# PoE.net
KiCad netlist of a schematic drawn in Altium Designer
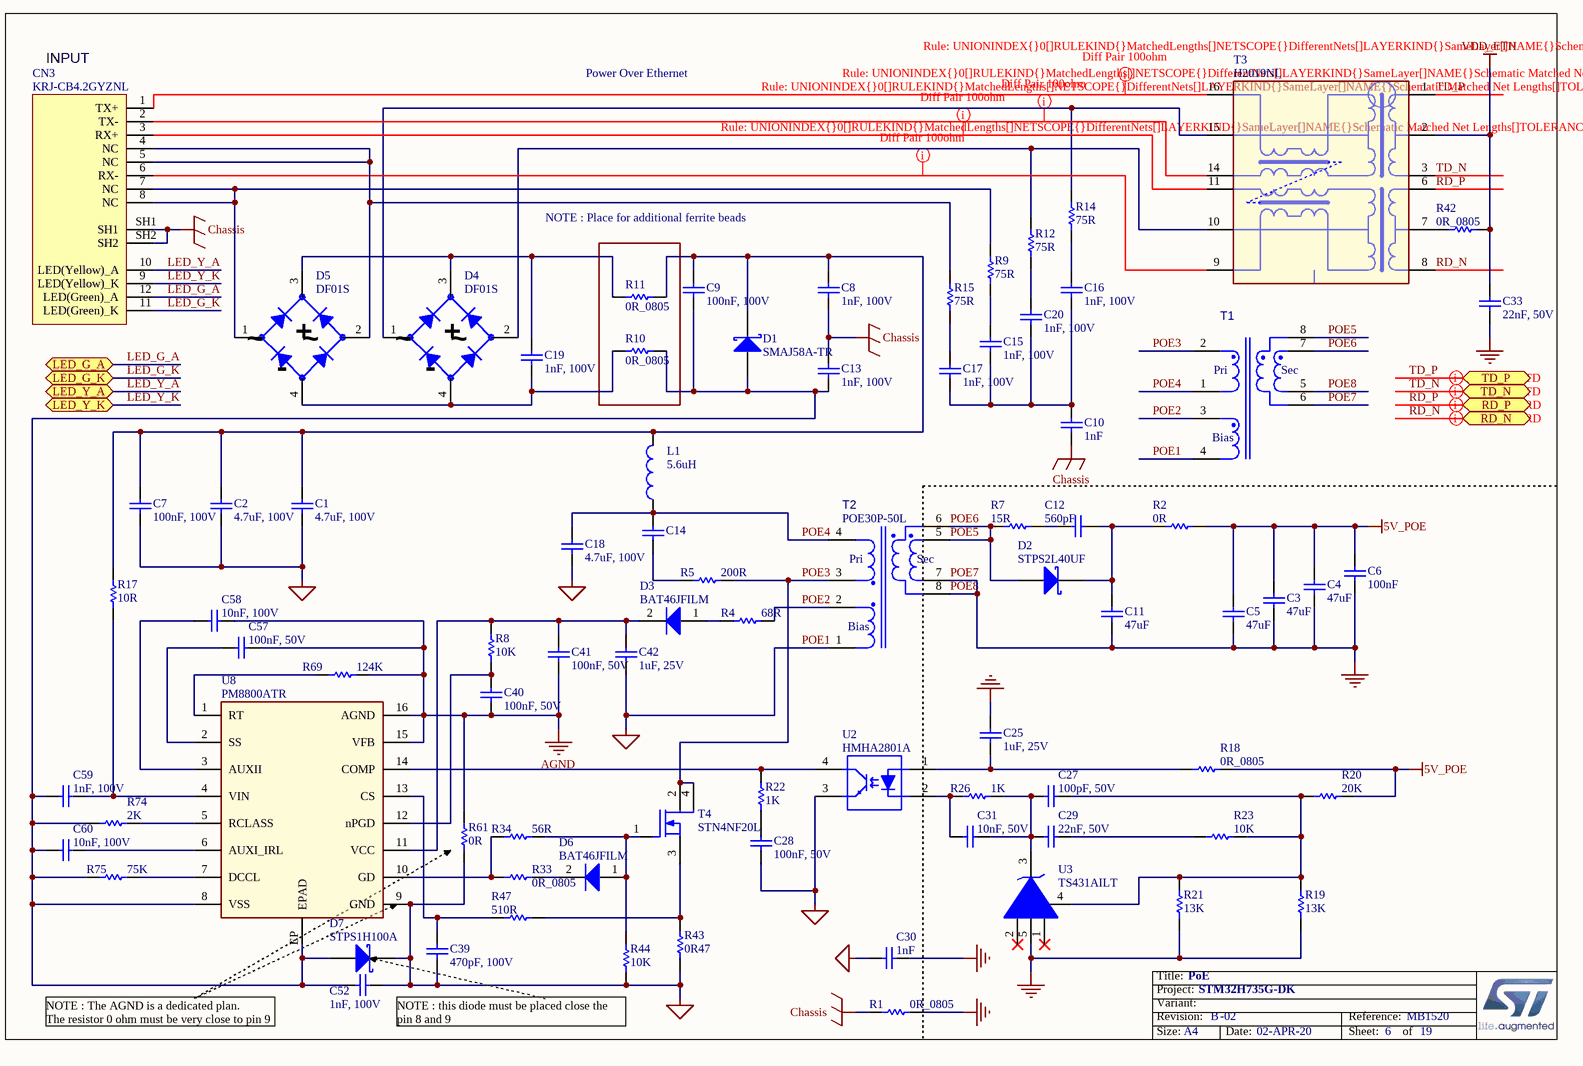
[diagram p0: PoE.SchDoc]

(export (version "E")
  (design (tool "Eeschema 10.0.6"))
  (components
    (comp (ref "C1")
      (value "4.7uF, 100V")
      (footprint "C1210")
      (description "Capacitor,4.7uF,100V, X7S,20%,1210")
      (fields
        (field (name "INTERNAL_PART_NUMBER") "MCD-01172")
        (field (name "MANUFACTURER_PART_NUMBER") "12101Z475MAT2A")
        (field (name "PROVIDED_BY") "SUBCO")
      )
      (libsource (lib "MCD_PARTS_database") (part "Capacitor"))
    )
    (comp (ref "C2")
      (value "4.7uF, 100V")
      (footprint "C1210")
      (description "Capacitor,4.7uF,100V, X7S,20%,1210")
      (fields
        (field (name "INTERNAL_PART_NUMBER") "MCD-01172")
        (field (name "MANUFACTURER_PART_NUMBER") "12101Z475MAT2A")
        (field (name "PROVIDED_BY") "SUBCO")
      )
      (libsource (lib "MCD_PARTS_database") (part "Capacitor"))
    )
    (comp (ref "C3")
      (value "47uF")
      (footprint "C0805")
      (description "Capacitor, MLCC, 47uF, 10V, X5R, 20%, 0805, T=1,25mm")
      (fields
        (field (name "INTERNAL_PART_NUMBER") "MCD-00204")
        (field (name "MANUFACTURER_PART_NUMBER") "GRM21BR61A476ME15K")
        (field (name "PROVIDED_BY") "SUBCO")
      )
      (libsource (lib "MCD_PARTS_database") (part "Capacitor"))
    )
    (comp (ref "C4")
      (value "47uF")
      (footprint "C0805")
      (description "Capacitor, MLCC, 47uF, 10V, X5R, 20%, 0805, T=1,25mm")
      (fields
        (field (name "INTERNAL_PART_NUMBER") "MCD-00204")
        (field (name "MANUFACTURER_PART_NUMBER") "GRM21BR61A476ME15K")
        (field (name "PROVIDED_BY") "SUBCO")
      )
      (libsource (lib "MCD_PARTS_database") (part "Capacitor"))
    )
    (comp (ref "C5")
      (value "47uF")
      (footprint "C0805")
      (description "Capacitor, MLCC, 47uF, 10V, X5R, 20%, 0805, T=1,25mm")
      (fields
        (field (name "INTERNAL_PART_NUMBER") "MCD-00204")
        (field (name "MANUFACTURER_PART_NUMBER") "GRM21BR61A476ME15K")
        (field (name "PROVIDED_BY") "SUBCO")
      )
      (libsource (lib "MCD_PARTS_database") (part "Capacitor"))
    )
    (comp (ref "C6")
      (value "100nF")
      (footprint "C0603")
      (description "Capacitor, MLCC, 100nF, 16V, X7R, 10%, 0603, T=0,8mm")
      (fields
        (field (name "INTERNAL_PART_NUMBER") "MCD-00211")
        (field (name "MANUFACTURER_PART_NUMBER") "CC0603KRX7R7BB104")
        (field (name "PROVIDED_BY") "SUBCO")
      )
      (libsource (lib "MCD_PARTS_database") (part "Capacitor"))
    )
    (comp (ref "C7")
      (value "100nF, 100V")
      (footprint "C0805")
      (description "Capacitor,100nF,100V,X7R,10%,0805")
      (fields
        (field (name "INTERNAL_PART_NUMBER") "MCD-01093")
        (field (name "MANUFACTURER_PART_NUMBER") "C2012X7R2A104K125AA")
        (field (name "PROVIDED_BY") "SUBCO")
      )
      (libsource (lib "MCD_PARTS_database") (part "Capacitor"))
    )
    (comp (ref "C8")
      (value "1nF, 100V")
      (footprint "C0603")
      (description "Capacitor,1nF,100V,X7R,10%,0603")
      (fields
        (field (name "INTERNAL_PART_NUMBER") "MCD-01091")
        (field (name "MANUFACTURER_PART_NUMBER") "CC0603KRX7R0BB102")
        (field (name "PROVIDED_BY") "SUBCO")
      )
      (libsource (lib "MCD_PARTS_database") (part "Capacitor"))
    )
    (comp (ref "C9")
      (value "100nF, 100V")
      (footprint "C0805")
      (description "Capacitor,100nF,100V,X7R,10%,0805")
      (fields
        (field (name "INTERNAL_PART_NUMBER") "MCD-01093")
        (field (name "MANUFACTURER_PART_NUMBER") "C2012X7R2A104K125AA")
        (field (name "PROVIDED_BY") "SUBCO")
      )
      (libsource (lib "MCD_PARTS_database") (part "Capacitor"))
    )
    (comp (ref "C10")
      (value "1nF")
      (footprint "C1206_H1P6")
      (description "Capacitor, MLCC, 1nF, 2KV, X7R, 10%, 1206, T=1,25mm")
      (fields
        (field (name "INTERNAL_PART_NUMBER") "MCD-00722")
        (field (name "MANUFACTURER_PART_NUMBER") "CC1206KKX7RDBB102")
        (field (name "PROVIDED_BY") "SUBCO")
      )
      (libsource (lib "MCD_PARTS_database") (part "Capacitor"))
    )
    (comp (ref "C11")
      (value "47uF")
      (footprint "C0805")
      (description "Capacitor, MLCC, 47uF, 10V, X5R, 20%, 0805, T=1,25mm")
      (fields
        (field (name "INTERNAL_PART_NUMBER") "MCD-00204")
        (field (name "MANUFACTURER_PART_NUMBER") "GRM21BR61A476ME15K")
        (field (name "PROVIDED_BY") "SUBCO")
      )
      (libsource (lib "MCD_PARTS_database") (part "Capacitor"))
    )
    (comp (ref "C12")
      (value "560pF")
      (footprint "C0603")
      (description "Capacitor,560pF,16V,X7R,10%,0603")
      (fields
        (field (name "INTERNAL_PART_NUMBER") "MCD-01095")
        (field (name "MANUFACTURER_PART_NUMBER") "0603YC561KAT2A")
        (field (name "PROVIDED_BY") "SUBCO")
      )
      (libsource (lib "MCD_PARTS_database") (part "Capacitor"))
    )
    (comp (ref "C13")
      (value "1nF, 100V")
      (footprint "C0603")
      (description "Capacitor,1nF,100V,X7R,10%,0603")
      (fields
        (field (name "INTERNAL_PART_NUMBER") "MCD-01091")
        (field (name "MANUFACTURER_PART_NUMBER") "CC0603KRX7R0BB102")
        (field (name "PROVIDED_BY") "SUBCO")
      )
      (libsource (lib "MCD_PARTS_database") (part "Capacitor"))
    )
    (comp (ref "C14")
      (value "Capacitor")
      (footprint "C0603")
      (description "Capacitor,27pF,100V,NPO,5%,0603")
      (fields
        (field (name "INTERNAL_PART_NUMBER") "MCD-01096")
        (field (name "MANUFACTURER_PART_NUMBER") "CC0603JRNPO0BN270")
        (field (name "PROVIDED_BY") "SUBCO")
      )
      (libsource (lib "MCD_PARTS_database") (part "Capacitor"))
    )
    (comp (ref "C15")
      (value "1nF, 100V")
      (footprint "C0603")
      (description "Capacitor,1nF,100V,X7R,10%,0603")
      (fields
        (field (name "INTERNAL_PART_NUMBER") "MCD-01091")
        (field (name "MANUFACTURER_PART_NUMBER") "CC0603KRX7R0BB102")
        (field (name "PROVIDED_BY") "SUBCO")
      )
      (libsource (lib "MCD_PARTS_database") (part "Capacitor"))
    )
    (comp (ref "C16")
      (value "1nF, 100V")
      (footprint "C0603")
      (description "Capacitor,1nF,100V,X7R,10%,0603")
      (fields
        (field (name "INTERNAL_PART_NUMBER") "MCD-01091")
        (field (name "MANUFACTURER_PART_NUMBER") "CC0603KRX7R0BB102")
        (field (name "PROVIDED_BY") "SUBCO")
      )
      (libsource (lib "MCD_PARTS_database") (part "Capacitor"))
    )
    (comp (ref "C17")
      (value "1nF, 100V")
      (footprint "C0603")
      (description "Capacitor,1nF,100V,X7R,10%,0603")
      (fields
        (field (name "INTERNAL_PART_NUMBER") "MCD-01091")
        (field (name "MANUFACTURER_PART_NUMBER") "CC0603KRX7R0BB102")
        (field (name "PROVIDED_BY") "SUBCO")
      )
      (libsource (lib "MCD_PARTS_database") (part "Capacitor"))
    )
    (comp (ref "C18")
      (value "4.7uF, 100V")
      (footprint "C1210")
      (description "Capacitor,4.7uF,100V, X7S,20%,1210")
      (fields
        (field (name "INTERNAL_PART_NUMBER") "MCD-01172")
        (field (name "MANUFACTURER_PART_NUMBER") "12101Z475MAT2A")
        (field (name "PROVIDED_BY") "SUBCO")
      )
      (libsource (lib "MCD_PARTS_database") (part "Capacitor"))
    )
    (comp (ref "C19")
      (value "1nF, 100V")
      (footprint "C0603")
      (description "Capacitor,1nF,100V,X7R,10%,0603")
      (fields
        (field (name "INTERNAL_PART_NUMBER") "MCD-01091")
        (field (name "MANUFACTURER_PART_NUMBER") "CC0603KRX7R0BB102")
        (field (name "PROVIDED_BY") "SUBCO")
      )
      (libsource (lib "MCD_PARTS_database") (part "Capacitor"))
    )
    (comp (ref "C20")
      (value "1nF, 100V")
      (footprint "C0603")
      (description "Capacitor,1nF,100V,X7R,10%,0603")
      (fields
        (field (name "INTERNAL_PART_NUMBER") "MCD-01091")
        (field (name "MANUFACTURER_PART_NUMBER") "CC0603KRX7R0BB102")
        (field (name "PROVIDED_BY") "SUBCO")
      )
      (libsource (lib "MCD_PARTS_database") (part "Capacitor"))
    )
    (comp (ref "C25")
      (value "1uF, 25V")
      (footprint "C0603")
      (description "Capacitor,1uF,25V,X5R,10%,0603")
      (fields
        (field (name "INTERNAL_PART_NUMBER") "MCD-01100")
        (field (name "MANUFACTURER_PART_NUMBER") "CC0603KRX5R8BB105")
        (field (name "PROVIDED_BY") "SUBCO")
      )
      (libsource (lib "MCD_PARTS_database") (part "Capacitor"))
    )
    (comp (ref "C27")
      (value "100pF, 50V")
      (footprint "C0603")
      (description "Capacitor,100pF,50V,X7R,10%,0603")
      (fields
        (field (name "INTERNAL_PART_NUMBER") "MCD-01101")
        (field (name "MANUFACTURER_PART_NUMBER") "06035C101JAT4A")
        (field (name "PROVIDED_BY") "SUBCO")
      )
      (libsource (lib "MCD_PARTS_database") (part "Capacitor"))
    )
    (comp (ref "C28")
      (value "100nF, 50V")
      (footprint "C0603")
      (description "Capacitor,100nF,50V,X7R,10%,0603")
      (fields
        (field (name "INTERNAL_PART_NUMBER") "MCD-01099")
        (field (name "MANUFACTURER_PART_NUMBER") "CC0603KRX7R9BB104")
        (field (name "PROVIDED_BY") "SUBCO")
      )
      (libsource (lib "MCD_PARTS_database") (part "Capacitor"))
    )
    (comp (ref "C29")
      (value "22nF, 50V")
      (footprint "C0603")
      (description "Capacitor,22nF,50V,X7R,10%,0603")
      (fields
        (field (name "INTERNAL_PART_NUMBER") "MCD-01103")
        (field (name "MANUFACTURER_PART_NUMBER") "CC0603KRX7R9BB223")
        (field (name "PROVIDED_BY") "SUBCO")
      )
      (libsource (lib "MCD_PARTS_database") (part "Capacitor"))
    )
    (comp (ref "C30")
      (value "1nF")
      (footprint "C1206_H1P6")
      (description "Capacitor, MLCC, 1nF, 2KV, X7R, 10%, 1206, T=1,25mm")
      (fields
        (field (name "INTERNAL_PART_NUMBER") "MCD-00722")
        (field (name "MANUFACTURER_PART_NUMBER") "CC1206KKX7RDBB102")
        (field (name "PROVIDED_BY") "SUBCO")
      )
      (libsource (lib "MCD_PARTS_database") (part "Capacitor"))
    )
    (comp (ref "C31")
      (value "10nF, 50V")
      (footprint "C0603")
      (description "Capacitor,10nF,50V,X7R,10%,0603")
      (fields
        (field (name "INTERNAL_PART_NUMBER") "MCD-01102")
        (field (name "MANUFACTURER_PART_NUMBER") "CC0603KRX7R9BB103")
        (field (name "PROVIDED_BY") "SUBCO")
      )
      (libsource (lib "MCD_PARTS_database") (part "Capacitor"))
    )
    (comp (ref "C33")
      (value "22nF, 50V")
      (footprint "C0603")
      (description "Capacitor,22nF,50V,X7R,10%,0603")
      (fields
        (field (name "INTERNAL_PART_NUMBER") "MCD-01103")
        (field (name "MANUFACTURER_PART_NUMBER") "CC0603KRX7R9BB223")
        (field (name "PROVIDED_BY") "SUBCO")
      )
      (libsource (lib "MCD_PARTS_database") (part "Capacitor"))
    )
    (comp (ref "C39")
      (value "470pF, 100V")
      (footprint "C0603")
      (description "Capacitor,470pF,100V,X7R,10%,0603")
      (fields
        (field (name "INTERNAL_PART_NUMBER") "MCD-01104")
        (field (name "MANUFACTURER_PART_NUMBER") "06031C471KAT2A")
        (field (name "PROVIDED_BY") "SUBCO")
      )
      (libsource (lib "MCD_PARTS_database") (part "Capacitor"))
    )
    (comp (ref "C40")
      (value "100nF, 50V")
      (footprint "C0603")
      (description "Capacitor,100nF,50V,X7R,10%,0603")
      (fields
        (field (name "INTERNAL_PART_NUMBER") "MCD-01099")
        (field (name "MANUFACTURER_PART_NUMBER") "CC0603KRX7R9BB104")
        (field (name "PROVIDED_BY") "SUBCO")
      )
      (libsource (lib "MCD_PARTS_database") (part "Capacitor"))
    )
    (comp (ref "C41")
      (value "100nF, 50V")
      (footprint "C0603")
      (description "Capacitor,100nF,50V,X7R,10%,0603")
      (fields
        (field (name "INTERNAL_PART_NUMBER") "MCD-01099")
        (field (name "MANUFACTURER_PART_NUMBER") "CC0603KRX7R9BB104")
        (field (name "PROVIDED_BY") "SUBCO")
      )
      (libsource (lib "MCD_PARTS_database") (part "Capacitor"))
    )
    (comp (ref "C42")
      (value "1uF, 25V")
      (footprint "C0603")
      (description "Capacitor,1uF,25V,X5R,10%,0603")
      (fields
        (field (name "INTERNAL_PART_NUMBER") "MCD-01100")
        (field (name "MANUFACTURER_PART_NUMBER") "CC0603KRX5R8BB105")
        (field (name "PROVIDED_BY") "SUBCO")
      )
      (libsource (lib "MCD_PARTS_database") (part "Capacitor"))
    )
    (comp (ref "C52")
      (value "1nF, 100V")
      (footprint "C0603")
      (description "Capacitor,1nF,100V,X7R,10%,0603")
      (fields
        (field (name "INTERNAL_PART_NUMBER") "MCD-01091")
        (field (name "MANUFACTURER_PART_NUMBER") "CC0603KRX7R0BB102")
        (field (name "PROVIDED_BY") "SUBCO")
      )
      (libsource (lib "MCD_PARTS_database") (part "Capacitor"))
    )
    (comp (ref "C57")
      (value "100nF, 50V")
      (footprint "C0603")
      (description "Capacitor,100nF,50V,X7R,10%,0603")
      (fields
        (field (name "INTERNAL_PART_NUMBER") "MCD-01099")
        (field (name "MANUFACTURER_PART_NUMBER") "CC0603KRX7R9BB104")
        (field (name "PROVIDED_BY") "SUBCO")
      )
      (libsource (lib "MCD_PARTS_database") (part "Capacitor"))
    )
    (comp (ref "C58")
      (value "10nF, 100V")
      (footprint "C0603")
      (description "Capacitor,10nF,100V,X7R,10%,0603")
      (fields
        (field (name "INTERNAL_PART_NUMBER") "MCD-01098")
        (field (name "MANUFACTURER_PART_NUMBER") "CC0603KRX7R0BB103")
        (field (name "PROVIDED_BY") "SUBCO")
      )
      (libsource (lib "MCD_PARTS_database") (part "Capacitor"))
    )
    (comp (ref "C59")
      (value "1nF, 100V")
      (footprint "C0603")
      (description "Capacitor,1nF,100V,X7R,10%,0603")
      (fields
        (field (name "INTERNAL_PART_NUMBER") "MCD-01091")
        (field (name "MANUFACTURER_PART_NUMBER") "CC0603KRX7R0BB102")
        (field (name "PROVIDED_BY") "SUBCO")
      )
      (libsource (lib "MCD_PARTS_database") (part "Capacitor"))
    )
    (comp (ref "C60")
      (value "10nF, 100V")
      (footprint "C0603")
      (description "Capacitor,10nF,100V,X7R,10%,0603")
      (fields
        (field (name "INTERNAL_PART_NUMBER") "MCD-01098")
        (field (name "MANUFACTURER_PART_NUMBER") "CC0603KRX7R0BB103")
        (field (name "PROVIDED_BY") "SUBCO")
      )
      (libsource (lib "MCD_PARTS_database") (part "Capacitor"))
    )
    (comp (ref "CN3")
      (value "KRJ-CB4.2GYZNL")
      (footprint "CON_RJ45_DGKYD_KRJ-CB4.2GYZNL")
      (description "RJ45 jack, single port, with LEDS, Metal shielded dip low profile")
      (fields
        (field (name "INTERNAL_PART_NUMBER") "MCD-00717")
        (field (name "MANUFACTURER") "DONGGUAN KEYOUDA ELECTRONIC TECHNOLOGY")
        (field (name "PROVIDED_BY") "SUBCO")
      )
      (libsource (lib "MCD_PARTS_database") (part "RJ45_KRJ-CB4.2GYZNL"))
    )
    (comp (ref "D1")
      (value "SMAJ58A-TR")
      (footprint "DIO_SMA_1A_2K")
      (description "Transil 400W, VRM=58V")
      (fields
        (field (name "INTERNAL_PART_NUMBER") "MCD-01083")
        (field (name "MANUFACTURER") "STMICROELECTRONICS")
        (field (name "PROVIDED_BY") "SUBCO with ST control")
      )
      (libsource (lib "MCD_PARTS_database") (part "SMAJ58A-TR"))
    )
    (comp (ref "D2")
      (value "STPS2L40UF")
      (footprint "DIO_SMB-FLAT_1A_2K")
      (description "Low drop power Schottky rectifier(2A, 40V, 0.34V)")
      (fields
        (field (name "INTERNAL_PART_NUMBER") "MCD-01087")
        (field (name "MANUFACTURER") "STMICROELECTRONICS")
        (field (name "PROVIDED_BY") "SUBCO with ST control")
      )
      (libsource (lib "MCD_PARTS_database") (part "STPS2L40UF"))
    )
    (comp (ref "D3")
      (value "BAT46JFILM")
      (footprint "DIO_SOD323_1A_2K")
      (description "Schottky Single diode,150mA, 100V")
      (fields
        (field (name "INTERNAL_PART_NUMBER") "MCD-01064")
        (field (name "MANUFACTURER") "STMICROELECTRONICS")
        (field (name "PROVIDED_BY") "SUBCO with ST control")
      )
      (libsource (lib "MCD_PARTS_database") (part "DIODE_1A_2K"))
    )
    (comp (ref "D4")
      (value "DF01S")
      (footprint "BRF_VISHAY_DFS_DF01S")
      (description "Surface Mount Bridge Rectifiers")
      (fields
        (field (name "INTERNAL_PART_NUMBER") "MCD-01065")
        (field (name "MANUFACTURER") "VISHAY")
        (field (name "PROVIDED_BY") "SUBCO")
      )
      (libsource (lib "MCD_PARTS_database") (part "DF01S"))
    )
    (comp (ref "D5")
      (value "DF01S")
      (footprint "BRF_VISHAY_DFS_DF01S")
      (description "Surface Mount Bridge Rectifiers")
      (fields
        (field (name "INTERNAL_PART_NUMBER") "MCD-01065")
        (field (name "MANUFACTURER") "VISHAY")
        (field (name "PROVIDED_BY") "SUBCO")
      )
      (libsource (lib "MCD_PARTS_database") (part "DF01S"))
    )
    (comp (ref "D6")
      (value "BAT46JFILM")
      (footprint "DIO_SOD323_1A_2K")
      (description "Schottky Single diode,150mA, 100V")
      (fields
        (field (name "INTERNAL_PART_NUMBER") "MCD-01064")
        (field (name "MANUFACTURER") "STMICROELECTRONICS")
        (field (name "PROVIDED_BY") "SUBCO with ST control")
      )
      (libsource (lib "MCD_PARTS_database") (part "DIODE_1A_2K"))
    )
    (comp (ref "D7")
      (value "STPS1H100A")
      (footprint "DIO_SMA_DO214-AC_1A_2K")
      (description "High voltage power Schottky rectifier")
      (fields
        (field (name "INTERNAL_PART_NUMBER") "MCD-01165")
        (field (name "MANUFACTURER") "STMICROELECTRONICS")
        (field (name "PROVIDED_BY") "SUBCO with ST control")
      )
      (libsource (lib "MCD_PARTS_database") (part "SMAJ58A-TR"))
    )
    (comp (ref "L1")
      (value "5.6uH")
      (footprint "IND_POWER_COILCRAFT_ME3220")
      (description "Power Inductor, 5.6uH, 0.2R, ME3220-562ML")
      (fields
        (field (name "INTERNAL_PART_NUMBER") "MCD-01109")
        (field (name "MANUFACTURER_PART_NUMBER") "ME3220-562ML")
        (field (name "PROVIDED_BY") "SUBCO")
      )
      (libsource (lib "MCD_PARTS_database") (part "Inductor"))
    )
    (comp (ref "R1")
      (value "0R_0805")
      (footprint "R0805")
      (description "Resistor,0R,0805,5%")
      (fields
        (field (name "INTERNAL_PART_NUMBER") "MCD-00179")
        (field (name "MANUFACTURER_PART_NUMBER") "RC0805JR-070RL")
        (field (name "PROVIDED_BY") "SUBCO")
      )
      (libsource (lib "MCD_PARTS_database") (part "Resistor"))
    )
    (comp (ref "R2")
      (value "0R")
      (footprint "R0603")
      (description "Resistor,0R,0603,5%,1/10W")
      (fields
        (field (name "INTERNAL_PART_NUMBER") "MCD-00056")
        (field (name "MANUFACTURER_PART_NUMBER") "RC0603JR-070RL")
        (field (name "PROVIDED_BY") "SUBCO")
      )
      (libsource (lib "MCD_PARTS_database") (part "Resistor"))
    )
    (comp (ref "R4")
      (value "68R")
      (footprint "R0805")
      (description "Resistor,68R,0805,1%")
      (fields
        (field (name "INTERNAL_PART_NUMBER") "MCD-01115")
        (field (name "MANUFACTURER_PART_NUMBER") "RC0805FR-0768RL")
        (field (name "PROVIDED_BY") "SUBCO")
      )
      (libsource (lib "MCD_PARTS_database") (part "Resistor"))
    )
    (comp (ref "R5")
      (value "200R")
      (footprint "R1206_H0P55")
      (description "Resistor,200R,1206,1%")
      (fields
        (field (name "INTERNAL_PART_NUMBER") "MCD-01114")
        (field (name "MANUFACTURER_PART_NUMBER") "LTR18EZPF2000")
        (field (name "PROVIDED_BY") "SUBCO")
      )
      (libsource (lib "MCD_PARTS_database") (part "Resistor"))
    )
    (comp (ref "R7")
      (value "15R")
      (footprint "R0805")
      (description "Resistor,15R,0805,1%")
      (fields
        (field (name "INTERNAL_PART_NUMBER") "MCD-01113")
        (field (name "MANUFACTURER_PART_NUMBER") "RC0805FR-0715RL")
        (field (name "PROVIDED_BY") "SUBCO")
      )
      (libsource (lib "MCD_PARTS_database") (part "Resistor"))
    )
    (comp (ref "R8")
      (value "10K")
      (footprint "R0603")
      (description "Resistor,10K,0603,1%,1/10W")
      (fields
        (field (name "INTERNAL_PART_NUMBER") "MCD-00220")
        (field (name "MANUFACTURER_PART_NUMBER") "RC0603FR-0710KL")
        (field (name "PROVIDED_BY") "SUBCO")
      )
      (libsource (lib "MCD_PARTS_database") (part "Resistor"))
    )
    (comp (ref "R9")
      (value "75R")
      (footprint "R0805")
      (description "Resistor,75R,0805,1%")
      (fields
        (field (name "INTERNAL_PART_NUMBER") "MCD-01112")
        (field (name "MANUFACTURER_PART_NUMBER") "RC0805FR-0775RL")
        (field (name "PROVIDED_BY") "SUBCO")
      )
      (libsource (lib "MCD_PARTS_database") (part "Resistor"))
    )
    (comp (ref "R10")
      (value "0R_0805")
      (footprint "R0805")
      (description "Resistor,0R,0805,5%")
      (fields
        (field (name "INTERNAL_PART_NUMBER") "MCD-00179")
        (field (name "MANUFACTURER_PART_NUMBER") "RC0805JR-070RL")
        (field (name "PROVIDED_BY") "SUBCO")
      )
      (libsource (lib "MCD_PARTS_database") (part "Resistor"))
    )
    (comp (ref "R11")
      (value "0R_0805")
      (footprint "R0805")
      (description "Resistor,0R,0805,5%")
      (fields
        (field (name "INTERNAL_PART_NUMBER") "MCD-00179")
        (field (name "MANUFACTURER_PART_NUMBER") "RC0805JR-070RL")
        (field (name "PROVIDED_BY") "SUBCO")
      )
      (libsource (lib "MCD_PARTS_database") (part "Resistor"))
    )
    (comp (ref "R12")
      (value "75R")
      (footprint "R0805")
      (description "Resistor,75R,0805,1%")
      (fields
        (field (name "INTERNAL_PART_NUMBER") "MCD-01112")
        (field (name "MANUFACTURER_PART_NUMBER") "RC0805FR-0775RL")
        (field (name "PROVIDED_BY") "SUBCO")
      )
      (libsource (lib "MCD_PARTS_database") (part "Resistor"))
    )
    (comp (ref "R14")
      (value "75R")
      (footprint "R0805")
      (description "Resistor,75R,0805,1%")
      (fields
        (field (name "INTERNAL_PART_NUMBER") "MCD-01112")
        (field (name "MANUFACTURER_PART_NUMBER") "RC0805FR-0775RL")
        (field (name "PROVIDED_BY") "SUBCO")
      )
      (libsource (lib "MCD_PARTS_database") (part "Resistor"))
    )
    (comp (ref "R15")
      (value "75R")
      (footprint "R0805")
      (description "Resistor,75R,0805,1%")
      (fields
        (field (name "INTERNAL_PART_NUMBER") "MCD-01112")
        (field (name "MANUFACTURER_PART_NUMBER") "RC0805FR-0775RL")
        (field (name "PROVIDED_BY") "SUBCO")
      )
      (libsource (lib "MCD_PARTS_database") (part "Resistor"))
    )
    (comp (ref "R17")
      (value "10R")
      (footprint "R0805")
      (description "Resistor,10R,0805,1%,Stackpole,1/4W")
      (fields
        (field (name "INTERNAL_PART_NUMBER") "MCD-01111")
        (field (name "MANUFACTURER_PART_NUMBER") "RNCP0805FTD10R0")
        (field (name "PROVIDED_BY") "SUBCO")
      )
      (libsource (lib "MCD_PARTS_database") (part "Resistor"))
    )
    (comp (ref "R18")
      (value "0R_0805")
      (footprint "R0805")
      (description "Resistor,0R,0805,5%")
      (fields
        (field (name "INTERNAL_PART_NUMBER") "MCD-00179")
        (field (name "MANUFACTURER_PART_NUMBER") "RC0805JR-070RL")
        (field (name "PROVIDED_BY") "SUBCO")
      )
      (libsource (lib "MCD_PARTS_database") (part "Resistor"))
    )
    (comp (ref "R19")
      (value "13K")
      (footprint "R0603")
      (description "Resistor,13K,0603,1%,1/10W")
      (fields
        (field (name "INTERNAL_PART_NUMBER") "MCD-00384")
        (field (name "MANUFACTURER_PART_NUMBER") "RC0603FR-0713KL")
        (field (name "PROVIDED_BY") "SUBCO")
      )
      (libsource (lib "MCD_PARTS_database") (part "Resistor"))
    )
    (comp (ref "R20")
      (value "20K")
      (footprint "R0603")
      (description "Resistor,20K,0603,1%,1/10W")
      (fields
        (field (name "INTERNAL_PART_NUMBER") "MCD-00422")
        (field (name "MANUFACTURER_PART_NUMBER") "RC0603FR-0720KL")
        (field (name "PROVIDED_BY") "SUBCO")
      )
      (libsource (lib "MCD_PARTS_database") (part "Resistor"))
    )
    (comp (ref "R21")
      (value "13K")
      (footprint "R0603")
      (description "Resistor,13K,0603,1%,1/10W")
      (fields
        (field (name "INTERNAL_PART_NUMBER") "MCD-00384")
        (field (name "MANUFACTURER_PART_NUMBER") "RC0603FR-0713KL")
        (field (name "PROVIDED_BY") "SUBCO")
      )
      (libsource (lib "MCD_PARTS_database") (part "Resistor"))
    )
    (comp (ref "R22")
      (value "1K")
      (footprint "R0603")
      (description "Resistor,1K,0603,1%,1/10W")
      (fields
        (field (name "INTERNAL_PART_NUMBER") "MCD-00070")
        (field (name "MANUFACTURER_PART_NUMBER") "RC0603FR-071KL")
        (field (name "PROVIDED_BY") "SUBCO")
      )
      (libsource (lib "MCD_PARTS_database") (part "Resistor"))
    )
    (comp (ref "R23")
      (value "10K")
      (footprint "R0603")
      (description "Resistor,10K,0603,1%,1/10W")
      (fields
        (field (name "INTERNAL_PART_NUMBER") "MCD-00220")
        (field (name "MANUFACTURER_PART_NUMBER") "RC0603FR-0710KL")
        (field (name "PROVIDED_BY") "SUBCO")
      )
      (libsource (lib "MCD_PARTS_database") (part "Resistor"))
    )
    (comp (ref "R26")
      (value "1K")
      (footprint "R0603")
      (description "Resistor,1K,0603,1%,1/10W")
      (fields
        (field (name "INTERNAL_PART_NUMBER") "MCD-00070")
        (field (name "MANUFACTURER_PART_NUMBER") "RC0603FR-071KL")
        (field (name "PROVIDED_BY") "SUBCO")
      )
      (libsource (lib "MCD_PARTS_database") (part "Resistor"))
    )
    (comp (ref "R33")
      (value "0R_0805")
      (footprint "R0805")
      (description "Resistor,0R,0805,5%")
      (fields
        (field (name "INTERNAL_PART_NUMBER") "MCD-00179")
        (field (name "MANUFACTURER_PART_NUMBER") "RC0805JR-070RL")
        (field (name "PROVIDED_BY") "SUBCO")
      )
      (libsource (lib "MCD_PARTS_database") (part "Resistor"))
    )
    (comp (ref "R34")
      (value "56R")
      (footprint "R0805")
      (description "Resistor,56R,0805,1%")
      (fields
        (field (name "INTERNAL_PART_NUMBER") "MCD-01118")
        (field (name "MANUFACTURER_PART_NUMBER") "RC0805FR-0756RL")
        (field (name "PROVIDED_BY") "SUBCO")
      )
      (libsource (lib "MCD_PARTS_database") (part "Resistor"))
    )
    (comp (ref "R42")
      (value "0R_0805")
      (footprint "R0805")
      (description "Resistor,0R,0805,5%")
      (fields
        (field (name "INTERNAL_PART_NUMBER") "MCD-00179")
        (field (name "MANUFACTURER_PART_NUMBER") "RC0805JR-070RL")
        (field (name "PROVIDED_BY") "SUBCO")
      )
      (libsource (lib "MCD_PARTS_database") (part "Resistor"))
    )
    (comp (ref "R43")
      (value "0R47")
      (footprint "R1206_H0P55")
      (description "Resistor,0.47R,1206,1%")
      (fields
        (field (name "INTERNAL_PART_NUMBER") "MCD-01119")
        (field (name "MANUFACTURER_PART_NUMBER") "RL1206FR-070R47L")
        (field (name "PROVIDED_BY") "SUBCO")
      )
      (libsource (lib "MCD_PARTS_database") (part "Resistor"))
    )
    (comp (ref "R44")
      (value "10K")
      (footprint "R0603")
      (description "Resistor,10K,0603,1%,1/10W")
      (fields
        (field (name "INTERNAL_PART_NUMBER") "MCD-00220")
        (field (name "MANUFACTURER_PART_NUMBER") "RC0603FR-0710KL")
        (field (name "PROVIDED_BY") "SUBCO")
      )
      (libsource (lib "MCD_PARTS_database") (part "Resistor"))
    )
    (comp (ref "R47")
      (value "510R")
      (footprint "R0603")
      (description "Resistor,510R,0603,1%,1/10W")
      (fields
        (field (name "INTERNAL_PART_NUMBER") "MCD-00225")
        (field (name "MANUFACTURER_PART_NUMBER") "RC0603FR-07510RL")
        (field (name "PROVIDED_BY") "SUBCO")
      )
      (libsource (lib "MCD_PARTS_database") (part "Resistor"))
    )
    (comp (ref "R61")
      (value "0R")
      (footprint "R0603")
      (description "Resistor,0R,0603,5%,1/10W")
      (fields
        (field (name "INTERNAL_PART_NUMBER") "MCD-00056")
        (field (name "MANUFACTURER_PART_NUMBER") "RC0603JR-070RL")
        (field (name "PROVIDED_BY") "SUBCO")
      )
      (libsource (lib "MCD_PARTS_database") (part "Resistor"))
    )
    (comp (ref "R69")
      (value "124K")
      (footprint "R0603")
      (description "Resistor,124K,0603,1%")
      (fields
        (field (name "INTERNAL_PART_NUMBER") "MCD-01116")
        (field (name "MANUFACTURER_PART_NUMBER") "RC0603FR-07124KL")
        (field (name "PROVIDED_BY") "SUBCO")
      )
      (libsource (lib "MCD_PARTS_database") (part "Resistor"))
    )
    (comp (ref "R74")
      (value "2K")
      (footprint "R0805")
      (description "Resistor,2K,0805,1%")
      (fields
        (field (name "INTERNAL_PART_NUMBER") "MCD-01117")
        (field (name "MANUFACTURER_PART_NUMBER") "RC0805FR-072KL")
        (field (name "PROVIDED_BY") "SUBCO")
      )
      (libsource (lib "MCD_PARTS_database") (part "Resistor"))
    )
    (comp (ref "R75")
      (value "75K")
      (footprint "R0603")
      (description "Resistor,75K,0603,1%,1/10W")
      (fields
        (field (name "INTERNAL_PART_NUMBER") "MCD-00522")
        (field (name "MANUFACTURER_PART_NUMBER") "RC0603FR-0775KL")
        (field (name "PROVIDED_BY") "SUBCO")
      )
      (libsource (lib "MCD_PARTS_database") (part "Resistor"))
    )
    (comp (ref "T1")
      (value "TRS_750315923")
      (footprint "TRS_WURTH_750315923")
      (description "Flyback Transformers for 3 Watt, PoE applications")
      (fields
        (field (name "INTERNAL_PART_NUMBER") "MCD-01063")
        (field (name "MANUFACTURER_PART_NUMBER") "750315923")
        (field (name "PROVIDED_BY") "SUBCO")
      )
      (libsource (lib "MCD_PARTS_database") (part "TRS_750315923"))
    )
    (comp (ref "T2")
      (value "POE30P-50L")
      (footprint "TRS_COILCRAFT_POE30P-50L")
      (description "Flyback Transformers for 3 Watt, PoE applications, CoilCraft Cyntec")
      (fields
        (field (name "INTERNAL_PART_NUMBER") "MCD-01081")
        (field (name "MANUFACTURER") "COILCRAFT")
        (field (name "PROVIDED_BY") "SUBCO")
      )
      (libsource (lib "MCD_PARTS_database") (part "POE30P-50L"))
    )
    (comp (ref "T3")
      (value "H2019NL")
      (footprint "TRS_PULSE_H2019NL")
      (description "10/100BASE-TX VoIP Magnetics Modules, Data Transformer")
      (fields
        (field (name "INTERNAL_PART_NUMBER") "MCD-01067")
        (field (name "MANUFACTURER") "PULSE")
        (field (name "PROVIDED_BY") "SUBCO")
      )
      (libsource (lib "MCD_PARTS_database") (part "H2019NL"))
    )
    (comp (ref "T4")
      (value "STN4NF20L")
      (footprint "MOS_SOT223-TAB")
      (description "Annel 200 V, 1.1ohm, 1 A, low gate charge STripFET II, Power MOSFET")
      (fields
        (field (name "INTERNAL_PART_NUMBER") "MCD-01086")
        (field (name "MANUFACTURER") "STMICROELECTRONICS")
        (field (name "PROVIDED_BY") "SUBCO with ST control")
      )
      (libsource (lib "MCD_PARTS_database") (part "STN4NF20L"))
    )
    (comp (ref "U2")
      (value "HMHA2801A")
      (footprint "OPT_MINI-FLAT_FAIRCHILD_HMHA2801A")
      (description "OPTOISOLATOR 3.7KV TRANSISTOR 4SMD")
      (fields
        (field (name "INTERNAL_PART_NUMBER") "MCD-01068")
        (field (name "MANUFACTURER") "FAIRCHILD")
        (field (name "PROVIDED_BY") "SUBCO")
      )
      (libsource (lib "MCD_PARTS_database") (part "HMHA2801A"))
    )
    (comp (ref "U3")
      (value "TS431AILT")
      (footprint "MOS_SOT23-5L")
      (description "Low voltage adjustable shunt reference")
      (fields
        (field (name "INTERNAL_PART_NUMBER") "MCD-01089")
        (field (name "MANUFACTURER") "STMICROELECTRONICS")
        (field (name "PROVIDED_BY") "SUBCO with ST control")
      )
      (libsource (lib "MCD_PARTS_database") (part "TS431AILT"))
    )
    (comp (ref "U8")
      (value "PM8800ATR")
      (footprint "ICC_HTSSOP16-EPAD_5X4P4_P065")
      (fields
        (field (name "INTERNAL_PART_NUMBER") "MCD-01080")
        (field (name "MANUFACTURER") "STMICROELECTRONICS")
        (field (name "BMS_PART_NUMBER") "9177966")
        (field (name "PROVIDED_BY") "SUBCO with ST control")
      )
      (libsource (lib "MCD_PARTS_database") (part "PM8800ATR"))
    )
  )
  (nets
    (net (code "1") (name "/LED_G_A") (class "Default")
      (node (ref "CN3") (pin "12") (pinfunction "LED(Green)_A_12") (pintype "passive"))
    )
    (net (code "2") (name "/LED_G_K") (class "Default")
      (node (ref "CN3") (pin "11") (pinfunction "LED(Green)_K_11") (pintype "passive"))
    )
    (net (code "3") (name "/LED_Y_A") (class "Default")
      (node (ref "CN3") (pin "10") (pinfunction "LED(Yellow)_A_10") (pintype "passive"))
    )
    (net (code "4") (name "/LED_Y_K") (class "Default")
      (node (ref "CN3") (pin "9") (pinfunction "LED(Yellow)_K_9") (pintype "passive"))
    )
    (net (code "5") (name "/POE2") (class "Default")
      (node (ref "R4") (pin "2") (pinfunction "2_2") (pintype "passive"))
      (node (ref "T1") (pin "3") (pinfunction "3_3") (pintype "passive"))
      (node (ref "T2") (pin "2") (pinfunction "2_2") (pintype "passive"))
    )
    (net (code "6") (name "/POE3") (class "Default")
      (node (ref "R5") (pin "2") (pinfunction "2_2") (pintype "passive"))
      (node (ref "T1") (pin "2") (pinfunction "2_2") (pintype "passive"))
      (node (ref "T2") (pin "3") (pinfunction "3_3") (pintype "passive"))
      (node (ref "T4") (pin "2") (pinfunction "D_2") (pintype "passive"))
      (node (ref "T4") (pin "4") (pinfunction "D_4") (pintype "passive"))
    )
    (net (code "7") (name "/POE4") (class "Default")
      (node (ref "C14") (pin "2") (pinfunction "2_2") (pintype "passive"))
      (node (ref "C18") (pin "2") (pinfunction "2_2") (pintype "passive"))
      (node (ref "L1") (pin "1") (pinfunction "1_1") (pintype "passive"))
      (node (ref "T1") (pin "1") (pinfunction "1_1") (pintype "passive"))
      (node (ref "T2") (pin "4") (pinfunction "4_4") (pintype "passive"))
    )
    (net (code "8") (name "/POE5") (class "Default")
      (node (ref "D2") (pin "1") (pinfunction "A_1") (pintype "passive"))
      (node (ref "R7") (pin "1") (pinfunction "1_1") (pintype "passive"))
      (node (ref "T1") (pin "7") (pinfunction "7_7") (pintype "passive"))
      (node (ref "T1") (pin "8") (pinfunction "8_8") (pintype "passive"))
      (node (ref "T2") (pin "5") (pinfunction "5_5") (pintype "passive"))
      (node (ref "T2") (pin "6") (pinfunction "6_6") (pintype "passive"))
    )
    (net (code "9") (name "/RD_N") (class "Default")
      (node (ref "T3") (pin "8") (pinfunction "rd-_8") (pintype "passive"))
    )
    (net (code "10") (name "/RD_P") (class "Default")
      (node (ref "T3") (pin "6") (pinfunction "rd+_6") (pintype "passive"))
    )
    (net (code "11") (name "/TD_N") (class "Default")
      (node (ref "T3") (pin "3") (pinfunction "td-_3") (pintype "passive"))
    )
    (net (code "12") (name "/TD_P") (class "Default")
      (node (ref "T3") (pin "1") (pinfunction "td+_1") (pintype "passive"))
    )
    (net (code "13") (name "5V_POE") (class "Default")
      (node (ref "C3") (pin "2") (pinfunction "2_2") (pintype "passive"))
      (node (ref "C4") (pin "2") (pinfunction "2_2") (pintype "passive"))
      (node (ref "C5") (pin "2") (pinfunction "2_2") (pintype "passive"))
      (node (ref "C6") (pin "2") (pinfunction "2_2") (pintype "passive"))
      (node (ref "R18") (pin "2") (pinfunction "2_2") (pintype "passive"))
      (node (ref "R2") (pin "2") (pinfunction "2_2") (pintype "passive"))
      (node (ref "R20") (pin "2") (pinfunction "2_2") (pintype "passive"))
    )
    (net (code "14") (name "AGND") (class "Default")
      (node (ref "C40") (pin "1") (pinfunction "1_1") (pintype "passive"))
      (node (ref "C41") (pin "1") (pinfunction "1_1") (pintype "passive"))
      (node (ref "C57") (pin "2") (pinfunction "2_2") (pintype "passive"))
      (node (ref "C58") (pin "2") (pinfunction "2_2") (pintype "passive"))
      (node (ref "R61") (pin "2") (pinfunction "2_2") (pintype "passive"))
      (node (ref "R69") (pin "2") (pinfunction "2_2") (pintype "passive"))
      (node (ref "U8") (pin "15") (pinfunction "VFB_15") (pintype "passive"))
      (node (ref "U8") (pin "16") (pinfunction "AGND_16") (pintype "passive"))
    )
    (net (code "15") (name "Chassis") (class "Default")
      (node (ref "C10") (pin "1") (pinfunction "1_1") (pintype "passive"))
      (node (ref "C13") (pin "2") (pinfunction "2_2") (pintype "passive"))
      (node (ref "C8") (pin "1") (pinfunction "1_1") (pintype "passive"))
      (node (ref "CN3") (pin "SH1") (pinfunction "SH1_SH1") (pintype "passive"))
      (node (ref "CN3") (pin "SH2") (pinfunction "SH2_SH2") (pintype "passive"))
      (node (ref "R1") (pin "1") (pinfunction "1_1") (pintype "passive"))
    )
    (net (code "16") (name "GND") (class "Default")
      (node (ref "C11") (pin "1") (pinfunction "1_1") (pintype "passive"))
      (node (ref "C25") (pin "2") (pinfunction "2_2") (pintype "passive"))
      (node (ref "C3") (pin "1") (pinfunction "1_1") (pintype "passive"))
      (node (ref "C30") (pin "2") (pinfunction "2_2") (pintype "passive"))
      (node (ref "C33") (pin "1") (pinfunction "1_1") (pintype "passive"))
      (node (ref "C4") (pin "1") (pinfunction "1_1") (pintype "passive"))
      (node (ref "C5") (pin "1") (pinfunction "1_1") (pintype "passive"))
      (node (ref "C6") (pin "1") (pinfunction "1_1") (pintype "passive"))
      (node (ref "R1") (pin "2") (pinfunction "2_2") (pintype "passive"))
      (node (ref "R19") (pin "2") (pinfunction "2_2") (pintype "passive"))
      (node (ref "R21") (pin "1") (pinfunction "1_1") (pintype "passive"))
      (node (ref "T1") (pin "5") (pinfunction "5_5") (pintype "passive"))
      (node (ref "T1") (pin "6") (pinfunction "6_6") (pintype "passive"))
      (node (ref "T2") (pin "7") (pinfunction "7_7") (pintype "passive"))
      (node (ref "T2") (pin "8") (pinfunction "8_8") (pintype "passive"))
      (node (ref "U3") (pin "5") (pinfunction "A_5") (pintype "passive"))
    )
    (net (code "17") (name "GND_POWER_IN") (class "Default")
      (node (ref "C1") (pin "1") (pinfunction "1_1") (pintype "passive"))
      (node (ref "C18") (pin "1") (pinfunction "1_1") (pintype "passive"))
      (node (ref "C2") (pin "1") (pinfunction "1_1") (pintype "passive"))
      (node (ref "C28") (pin "1") (pinfunction "1_1") (pintype "passive"))
      (node (ref "C30") (pin "1") (pinfunction "1_1") (pintype "passive"))
      (node (ref "C39") (pin "1") (pinfunction "1_1") (pintype "passive"))
      (node (ref "C42") (pin "1") (pinfunction "1_1") (pintype "passive"))
      (node (ref "C52") (pin "1") (pinfunction "1_1") (pintype "passive"))
      (node (ref "C7") (pin "1") (pinfunction "1_1") (pintype "passive"))
      (node (ref "D7") (pin "2") (pinfunction "K_2") (pintype "passive"))
      (node (ref "R43") (pin "1") (pinfunction "1_1") (pintype "passive"))
      (node (ref "R44") (pin "1") (pinfunction "1_1") (pintype "passive"))
      (node (ref "R61") (pin "1") (pinfunction "1_1") (pintype "passive"))
      (node (ref "T1") (pin "4") (pinfunction "4_4") (pintype "passive"))
      (node (ref "T2") (pin "1") (pinfunction "1_1") (pintype "passive"))
      (node (ref "U2") (pin "3") (pinfunction "Emitter_3") (pintype "passive"))
      (node (ref "U8") (pin "9") (pinfunction "GND_9") (pintype "passive"))
    )
    (net (code "18") (name "Net-(C10-Pad2)") (class "Default")
      (node (ref "C10") (pin "2") (pinfunction "2_2") (pintype "passive"))
      (node (ref "C15") (pin "1") (pinfunction "1_1") (pintype "passive"))
      (node (ref "C16") (pin "1") (pinfunction "1_1") (pintype "passive"))
      (node (ref "C17") (pin "1") (pinfunction "1_1") (pintype "passive"))
      (node (ref "C20") (pin "1") (pinfunction "1_1") (pintype "passive"))
    )
    (net (code "19") (name "Net-(C12-Pad1)") (class "Default")
      (node (ref "C12") (pin "1") (pinfunction "1_1") (pintype "passive"))
      (node (ref "R7") (pin "2") (pinfunction "2_2") (pintype "passive"))
    )
    (net (code "20") (name "Net-(C14-Pad1)") (class "Default")
      (node (ref "C14") (pin "1") (pinfunction "1_1") (pintype "passive"))
      (node (ref "R5") (pin "1") (pinfunction "1_1") (pintype "passive"))
    )
    (net (code "21") (name "Net-(C15-Pad2)") (class "Default")
      (node (ref "C15") (pin "2") (pinfunction "2_2") (pintype "passive"))
      (node (ref "R9") (pin "1") (pinfunction "1_1") (pintype "passive"))
    )
    (net (code "22") (name "Net-(C16-Pad2)") (class "Default")
      (node (ref "C16") (pin "2") (pinfunction "2_2") (pintype "passive"))
      (node (ref "R14") (pin "1") (pinfunction "1_1") (pintype "passive"))
    )
    (net (code "23") (name "Net-(C17-Pad2)") (class "Default")
      (node (ref "C17") (pin "2") (pinfunction "2_2") (pintype "passive"))
      (node (ref "R15") (pin "1") (pinfunction "1_1") (pintype "passive"))
    )
    (net (code "24") (name "Net-(C20-Pad2)") (class "Default")
      (node (ref "C20") (pin "2") (pinfunction "2_2") (pintype "passive"))
      (node (ref "R12") (pin "1") (pinfunction "1_1") (pintype "passive"))
    )
    (net (code "25") (name "Net-(C28-Pad2)") (class "Default")
      (node (ref "C28") (pin "2") (pinfunction "2_2") (pintype "passive"))
      (node (ref "R22") (pin "1") (pinfunction "1_1") (pintype "passive"))
    )
    (net (code "26") (name "Net-(C29-Pad2)") (class "Default")
      (node (ref "C29") (pin "2") (pinfunction "2_2") (pintype "passive"))
      (node (ref "R23") (pin "2") (pinfunction "2_2") (pintype "passive"))
    )
    (net (code "27") (name "Net-(CN3-RX+)") (class "Default")
      (node (ref "CN3") (pin "3") (pinfunction "RX+_3") (pintype "passive"))
      (node (ref "T3") (pin "11") (pinfunction "rx1+_11") (pintype "passive"))
    )
    (net (code "28") (name "Net-(CN3-RX-)") (class "Default")
      (node (ref "CN3") (pin "6") (pinfunction "RX-_6") (pintype "passive"))
      (node (ref "T3") (pin "9") (pinfunction "rx-_9") (pintype "passive"))
    )
    (net (code "29") (name "Net-(CN3-TX+)") (class "Default")
      (node (ref "CN3") (pin "1") (pinfunction "TX+_1") (pintype "passive"))
      (node (ref "T3") (pin "16") (pinfunction "tx1+_16") (pintype "passive"))
    )
    (net (code "30") (name "Net-(CN3-TX-)") (class "Default")
      (node (ref "CN3") (pin "2") (pinfunction "TX-_2") (pintype "passive"))
      (node (ref "T3") (pin "14") (pinfunction "tx1-_14") (pintype "passive"))
    )
    (net (code "31") (name "Net-(D1-A)") (class "Default")
      (node (ref "C13") (pin "1") (pinfunction "1_1") (pintype "passive"))
      (node (ref "C52") (pin "2") (pinfunction "2_2") (pintype "passive"))
      (node (ref "C59") (pin "2") (pinfunction "2_2") (pintype "passive"))
      (node (ref "C60") (pin "1") (pinfunction "1_1") (pintype "passive"))
      (node (ref "C9") (pin "2") (pinfunction "2_2") (pintype "passive"))
      (node (ref "D1") (pin "1") (pinfunction "A_1") (pintype "passive"))
      (node (ref "D7") (pin "1") (pinfunction "A_1") (pintype "passive"))
      (node (ref "R10") (pin "2") (pinfunction "2_2") (pintype "passive"))
      (node (ref "R74") (pin "1") (pinfunction "1_1") (pintype "passive"))
      (node (ref "R75") (pin "1") (pinfunction "1_1") (pintype "passive"))
      (node (ref "U8") (pin "8") (pinfunction "VSS_8") (pintype "passive"))
      (node (ref "U8") (pin "EP") (pinfunction "EPAD_EP") (pintype "passive"))
    )
    (net (code "32") (name "Net-(D1-K)") (class "Default")
      (node (ref "C1") (pin "2") (pinfunction "2_2") (pintype "passive"))
      (node (ref "C2") (pin "2") (pinfunction "2_2") (pintype "passive"))
      (node (ref "C7") (pin "2") (pinfunction "2_2") (pintype "passive"))
      (node (ref "C8") (pin "2") (pinfunction "2_2") (pintype "passive"))
      (node (ref "C9") (pin "1") (pinfunction "1_1") (pintype "passive"))
      (node (ref "D1") (pin "2") (pinfunction "K_2") (pintype "passive"))
      (node (ref "L1") (pin "2") (pinfunction "2_2") (pintype "passive"))
      (node (ref "R11") (pin "2") (pinfunction "2_2") (pintype "passive"))
      (node (ref "R17") (pin "2") (pinfunction "2_2") (pintype "passive"))
    )
    (net (code "33") (name "Net-(D2-K)") (class "Default")
      (node (ref "C11") (pin "2") (pinfunction "2_2") (pintype "passive"))
      (node (ref "C12") (pin "2") (pinfunction "2_2") (pintype "passive"))
      (node (ref "D2") (pin "2") (pinfunction "K_2") (pintype "passive"))
      (node (ref "R2") (pin "1") (pinfunction "1_1") (pintype "passive"))
    )
    (net (code "34") (name "Net-(D3-A)") (class "Default")
      (node (ref "D3") (pin "1") (pinfunction "A_1") (pintype "passive"))
      (node (ref "R4") (pin "1") (pinfunction "1_1") (pintype "passive"))
    )
    (net (code "35") (name "Net-(D3-K)") (class "Default")
      (node (ref "C41") (pin "2") (pinfunction "2_2") (pintype "passive"))
      (node (ref "C42") (pin "2") (pinfunction "2_2") (pintype "passive"))
      (node (ref "D3") (pin "2") (pinfunction "K_2") (pintype "passive"))
      (node (ref "R8") (pin "2") (pinfunction "2_2") (pintype "passive"))
      (node (ref "U8") (pin "11") (pinfunction "VCC_11") (pintype "passive"))
    )
    (net (code "36") (name "Net-(D4-AC_IN_1)") (class "Default")
      (node (ref "D4") (pin "1") (pinfunction "AC_IN_1_1") (pintype "passive"))
      (node (ref "R14") (pin "2") (pinfunction "2_2") (pintype "passive"))
      (node (ref "T3") (pin "15") (pinfunction "txct_15") (pintype "passive"))
    )
    (net (code "37") (name "Net-(D4-AC_IN_2)") (class "Default")
      (node (ref "D4") (pin "2") (pinfunction "AC_IN_2_2") (pintype "passive"))
      (node (ref "R12") (pin "2") (pinfunction "2_2") (pintype "passive"))
      (node (ref "T3") (pin "10") (pinfunction "rxct_10") (pintype "passive"))
    )
    (net (code "38") (name "Net-(D4-DC_OUT_MINUS)") (class "Default")
      (node (ref "C19") (pin "1") (pinfunction "1_1") (pintype "passive"))
      (node (ref "D4") (pin "4") (pinfunction "DC_OUT_MINUS_4") (pintype "passive"))
      (node (ref "D5") (pin "4") (pinfunction "DC_OUT_MINUS_4") (pintype "passive"))
      (node (ref "R10") (pin "1") (pinfunction "1_1") (pintype "passive"))
    )
    (net (code "39") (name "Net-(D4-DC_OUT_PLUS)") (class "Default")
      (node (ref "C19") (pin "2") (pinfunction "2_2") (pintype "passive"))
      (node (ref "D4") (pin "3") (pinfunction "DC_OUT_PLUS_3") (pintype "passive"))
      (node (ref "D5") (pin "3") (pinfunction "DC_OUT_PLUS_3") (pintype "passive"))
      (node (ref "R11") (pin "1") (pinfunction "1_1") (pintype "passive"))
    )
    (net (code "40") (name "Net-(D5-AC_IN_1)") (class "Default")
      (node (ref "CN3") (pin "7") (pinfunction "NC_7") (pintype "passive"))
      (node (ref "CN3") (pin "8") (pinfunction "NC_8") (pintype "passive"))
      (node (ref "D5") (pin "1") (pinfunction "AC_IN_1_1") (pintype "passive"))
      (node (ref "R9") (pin "2") (pinfunction "2_2") (pintype "passive"))
    )
    (net (code "41") (name "Net-(D5-AC_IN_2)") (class "Default")
      (node (ref "CN3") (pin "4") (pinfunction "NC_4") (pintype "passive"))
      (node (ref "CN3") (pin "5") (pinfunction "NC_5") (pintype "passive"))
      (node (ref "D5") (pin "2") (pinfunction "AC_IN_2_2") (pintype "passive"))
      (node (ref "R15") (pin "2") (pinfunction "2_2") (pintype "passive"))
    )
    (net (code "42") (name "Net-(D6-A)") (class "Default")
      (node (ref "D6") (pin "1") (pinfunction "A_1") (pintype "passive"))
      (node (ref "R34") (pin "2") (pinfunction "2_2") (pintype "passive"))
      (node (ref "R44") (pin "2") (pinfunction "2_2") (pintype "passive"))
      (node (ref "T4") (pin "1") (pinfunction "G_1") (pintype "passive"))
    )
    (net (code "43") (name "Net-(D6-K)") (class "Default")
      (node (ref "D6") (pin "2") (pinfunction "K_2") (pintype "passive"))
      (node (ref "R33") (pin "1") (pinfunction "1_1") (pintype "passive"))
    )
    (net (code "44") (name "Net-(T3-rct)") (class "Default")
      (node (ref "R42") (pin "1") (pinfunction "1_1") (pintype "passive"))
      (node (ref "T3") (pin "7") (pinfunction "rct_7") (pintype "passive"))
    )
    (net (code "45") (name "Net-(T4-S)") (class "Default")
      (node (ref "R43") (pin "2") (pinfunction "2_2") (pintype "passive"))
      (node (ref "R47") (pin "2") (pinfunction "2_2") (pintype "passive"))
      (node (ref "T4") (pin "3") (pinfunction "S_3") (pintype "passive"))
    )
    (net (code "46") (name "Net-(U2-Anode)") (class "Default")
      (node (ref "C25") (pin "1") (pinfunction "1_1") (pintype "passive"))
      (node (ref "R18") (pin "1") (pinfunction "1_1") (pintype "passive"))
      (node (ref "U2") (pin "1") (pinfunction "Anode_1") (pintype "passive"))
    )
    (net (code "47") (name "Net-(U2-B)") (class "Default")
      (node (ref "C31") (pin "1") (pinfunction "1_1") (pintype "passive"))
      (node (ref "R26") (pin "2") (pinfunction "2_2") (pintype "passive"))
      (node (ref "U2") (pin "2") (pinfunction "B_2") (pintype "passive"))
    )
    (net (code "48") (name "Net-(U2-Collector)") (class "Default")
      (node (ref "R22") (pin "2") (pinfunction "2_2") (pintype "passive"))
      (node (ref "U2") (pin "4") (pinfunction "Collector_4") (pintype "passive"))
      (node (ref "U8") (pin "14") (pinfunction "COMP_14") (pintype "passive"))
    )
    (net (code "49") (name "Net-(U3-K)") (class "Default")
      (node (ref "C27") (pin "1") (pinfunction "1_1") (pintype "passive"))
      (node (ref "C29") (pin "1") (pinfunction "1_1") (pintype "passive"))
      (node (ref "C31") (pin "2") (pinfunction "2_2") (pintype "passive"))
      (node (ref "R26") (pin "1") (pinfunction "1_1") (pintype "passive"))
      (node (ref "U3") (pin "3") (pinfunction "K_3") (pintype "passive"))
    )
    (net (code "50") (name "Net-(U3-REF)") (class "Default")
      (node (ref "C27") (pin "2") (pinfunction "2_2") (pintype "passive"))
      (node (ref "R19") (pin "1") (pinfunction "1_1") (pintype "passive"))
      (node (ref "R20") (pin "1") (pinfunction "1_1") (pintype "passive"))
      (node (ref "R21") (pin "2") (pinfunction "2_2") (pintype "passive"))
      (node (ref "R23") (pin "1") (pinfunction "1_1") (pintype "passive"))
      (node (ref "U3") (pin "4") (pinfunction "REF_4") (pintype "passive"))
    )
    (net (code "51") (name "Net-(U8-AUXII)") (class "Default")
      (node (ref "C58") (pin "1") (pinfunction "1_1") (pintype "passive"))
      (node (ref "U8") (pin "3") (pinfunction "AUXII_3") (pintype "passive"))
    )
    (net (code "52") (name "Net-(U8-AUXI_IRL)") (class "Default")
      (node (ref "C60") (pin "2") (pinfunction "2_2") (pintype "passive"))
      (node (ref "U8") (pin "6") (pinfunction "AUXI_IRL_6") (pintype "passive"))
    )
    (net (code "53") (name "Net-(U8-CS)") (class "Default")
      (node (ref "C39") (pin "2") (pinfunction "2_2") (pintype "passive"))
      (node (ref "R47") (pin "1") (pinfunction "1_1") (pintype "passive"))
      (node (ref "U8") (pin "13") (pinfunction "CS_13") (pintype "passive"))
    )
    (net (code "54") (name "Net-(U8-DCCL)") (class "Default")
      (node (ref "R75") (pin "2") (pinfunction "2_2") (pintype "passive"))
      (node (ref "U8") (pin "7") (pinfunction "DCCL_7") (pintype "passive"))
    )
    (net (code "55") (name "Net-(U8-GD)") (class "Default")
      (node (ref "R33") (pin "2") (pinfunction "2_2") (pintype "passive"))
      (node (ref "R34") (pin "1") (pinfunction "1_1") (pintype "passive"))
      (node (ref "U8") (pin "10") (pinfunction "GD_10") (pintype "passive"))
    )
    (net (code "56") (name "Net-(U8-RCLASS)") (class "Default")
      (node (ref "R74") (pin "2") (pinfunction "2_2") (pintype "passive"))
      (node (ref "U8") (pin "5") (pinfunction "RCLASS_5") (pintype "passive"))
    )
    (net (code "57") (name "Net-(U8-RT)") (class "Default")
      (node (ref "R69") (pin "1") (pinfunction "1_1") (pintype "passive"))
      (node (ref "U8") (pin "1") (pinfunction "RT_1") (pintype "passive"))
    )
    (net (code "58") (name "Net-(U8-SS)") (class "Default")
      (node (ref "C57") (pin "1") (pinfunction "1_1") (pintype "passive"))
      (node (ref "U8") (pin "2") (pinfunction "SS_2") (pintype "passive"))
    )
    (net (code "59") (name "Net-(U8-VIN)") (class "Default")
      (node (ref "C59") (pin "1") (pinfunction "1_1") (pintype "passive"))
      (node (ref "R17") (pin "1") (pinfunction "1_1") (pintype "passive"))
      (node (ref "U8") (pin "4") (pinfunction "VIN_4") (pintype "passive"))
    )
    (net (code "60") (name "Net-(U8-nPGD)") (class "Default")
      (node (ref "C40") (pin "2") (pinfunction "2_2") (pintype "passive"))
      (node (ref "R8") (pin "1") (pinfunction "1_1") (pintype "passive"))
      (node (ref "U8") (pin "12") (pinfunction "nPGD_12") (pintype "passive"))
    )
    (net (code "61") (name "VDD_ETH") (class "Default")
      (node (ref "C33") (pin "2") (pinfunction "2_2") (pintype "passive"))
      (node (ref "R42") (pin "2") (pinfunction "2_2") (pintype "passive"))
      (node (ref "T3") (pin "2") (pinfunction "tct_2") (pintype "passive"))
    )
    (net (code "62") (name "unconnected-(U3-NC-Pad1)") (class "Default")
      (node (ref "U3") (pin "1") (pinfunction "NC_1") (pintype "passive+no_connect"))
    )
    (net (code "63") (name "unconnected-(U3-NC-Pad2)") (class "Default")
      (node (ref "U3") (pin "2") (pinfunction "NC_2") (pintype "passive+no_connect"))
    )
  )
)
